# Thermocouple-Interface-5V.net
KiCad netlist of a schematic drawn in EAGLE
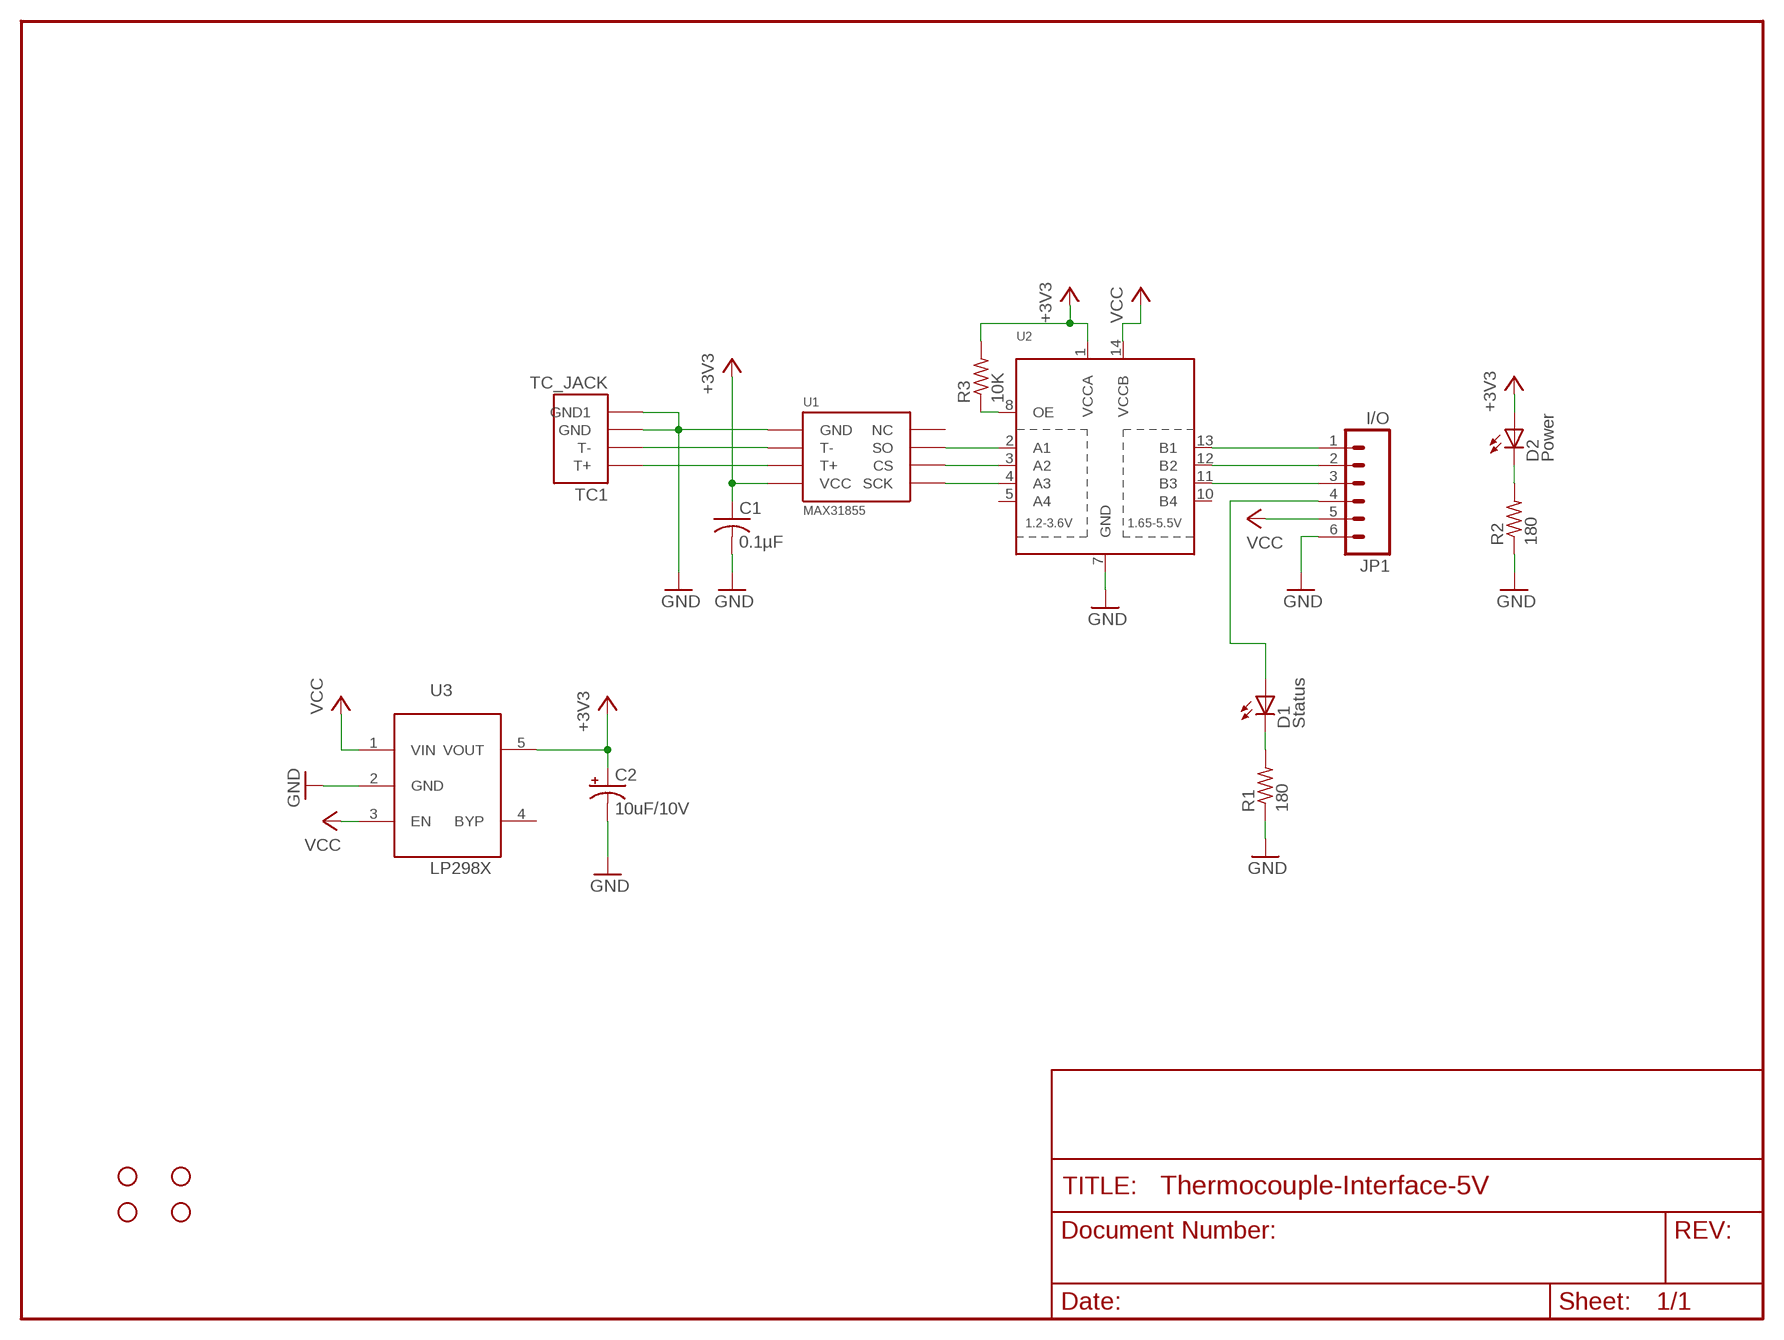
[diagram p0: schematic, sheet 1]

(export (version "E")
  (design (tool "Eeschema 10.0.6"))
  (components
    (comp (ref "C1")
      (value "0.1µF")
      (footprint "eagle-import:C0603")
      (libsource (lib "eagle-import") (part "C-USC0603"))
    )
    (comp (ref "C2")
      (value "10uF/10V")
      (footprint "eagle-import:A_3216-18R")
      (libsource (lib "eagle-import") (part "CPOL-USA/3216-18R"))
    )
    (comp (ref "D1")
      (value "Status")
      (footprint "eagle-import:CHIP-LED0805")
      (libsource (lib "eagle-import") (part "LEDCHIP-LED0805"))
    )
    (comp (ref "D2")
      (value "Power")
      (footprint "eagle-import:CHIP-LED0805")
      (libsource (lib "eagle-import") (part "LEDCHIP-LED0805"))
    )
    (comp (ref "JP1")
      (value "I/O")
      (footprint "eagle-import:1X06")
      (libsource (lib "eagle-import") (part "M06SIP"))
    )
    (comp (ref "R1")
      (value "180")
      (footprint "eagle-import:R0603")
      (libsource (lib "eagle-import") (part "R-US_R0603"))
    )
    (comp (ref "R2")
      (value "180")
      (footprint "eagle-import:R0603")
      (libsource (lib "eagle-import") (part "R-US_R0603"))
    )
    (comp (ref "R3")
      (value "10K")
      (footprint "eagle-import:R0603")
      (libsource (lib "eagle-import") (part "R-US_R0603"))
    )
    (comp (ref "TC1")
      (value "TC_JACK")
      (footprint "eagle-import:TC_JACK")
      (libsource (lib "eagle-import") (part "TC_JACK"))
    )
    (comp (ref "U$1")
      (value "STAND-OFF")
      (footprint "eagle-import:STAND-OFF")
      (libsource (lib "eagle-import") (part "STAND-OFF"))
    )
    (comp (ref "U$2")
      (value "STAND-OFF")
      (footprint "eagle-import:STAND-OFF")
      (libsource (lib "eagle-import") (part "STAND-OFF"))
    )
    (comp (ref "U$3")
      (value "STAND-OFF")
      (footprint "eagle-import:STAND-OFF")
      (libsource (lib "eagle-import") (part "STAND-OFF"))
    )
    (comp (ref "U$4")
      (value "STAND-OFF")
      (footprint "eagle-import:STAND-OFF")
      (libsource (lib "eagle-import") (part "STAND-OFF"))
    )
    (comp (ref "U1")
      (value "MAX31855")
      (footprint "eagle-import:SOIC-8")
      (libsource (lib "eagle-import") (part "MAX6675MAX31855"))
    )
    (comp (ref "U2")
      (value "TXB0104PWR")
      (footprint "eagle-import:TSSOP14")
      (libsource (lib "eagle-import") (part "TXB0104PWR"))
    )
    (comp (ref "U3")
      (value "LP298XS")
      (footprint "eagle-import:SOT23-5L")
      (libsource (lib "eagle-import") (part "LP298XS"))
    )
  )
  (nets
    (net (code "1") (name "+3V3") (class "Default")
      (node (ref "C1") (pin "1") (pinfunction "1_1") (pintype "passive"))
      (node (ref "C2") (pin "+") (pinfunction "+_+") (pintype "passive"))
      (node (ref "D2") (pin "A") (pinfunction "A_A") (pintype "passive"))
      (node (ref "R3") (pin "2") (pinfunction "2_2") (pintype "passive"))
      (node (ref "U1") (pin "VCC") (pinfunction "VCC_VCC") (pintype "bidirectional"))
      (node (ref "U2") (pin "1") (pinfunction "VCCA_1") (pintype "bidirectional"))
      (node (ref "U3") (pin "5") (pinfunction "VOUT_5") (pintype "bidirectional"))
    )
    (net (code "2") (name "GND") (class "Default")
      (node (ref "C1") (pin "2") (pinfunction "2_2") (pintype "passive"))
      (node (ref "C2") (pin "-") (pinfunction "-_-") (pintype "passive"))
      (node (ref "JP1") (pin "6") (pinfunction "6_6") (pintype "passive"))
      (node (ref "R1") (pin "1") (pinfunction "1_1") (pintype "passive"))
      (node (ref "R2") (pin "1") (pinfunction "1_1") (pintype "passive"))
      (node (ref "TC1") (pin "P$1") (pinfunction "GND_P$1") (pintype "bidirectional"))
      (node (ref "TC1") (pin "P$2") (pinfunction "GND1_P$2") (pintype "bidirectional"))
      (node (ref "U1") (pin "GND") (pinfunction "GND_GND") (pintype "bidirectional"))
      (node (ref "U2") (pin "7") (pinfunction "GND_7") (pintype "bidirectional"))
      (node (ref "U3") (pin "2") (pinfunction "GND_2") (pintype "bidirectional"))
    )
    (net (code "3") (name "Net-(D1-PadA)") (class "Default")
      (node (ref "D1") (pin "A") (pinfunction "A_A") (pintype "passive"))
      (node (ref "JP1") (pin "4") (pinfunction "4_4") (pintype "passive"))
    )
    (net (code "4") (name "Net-(D1-PadC)") (class "Default")
      (node (ref "D1") (pin "C") (pinfunction "C_C") (pintype "passive"))
      (node (ref "R1") (pin "2") (pinfunction "2_2") (pintype "passive"))
    )
    (net (code "5") (name "Net-(D2-PadC)") (class "Default")
      (node (ref "D2") (pin "C") (pinfunction "C_C") (pintype "passive"))
      (node (ref "R2") (pin "2") (pinfunction "2_2") (pintype "passive"))
    )
    (net (code "6") (name "Net-(TC1-PadT+)") (class "Default")
      (node (ref "TC1") (pin "T+") (pinfunction "T+_T+") (pintype "bidirectional"))
      (node (ref "U1") (pin "T+") (pinfunction "T+_T+") (pintype "bidirectional"))
    )
    (net (code "7") (name "Net-(TC1-PadT-)") (class "Default")
      (node (ref "TC1") (pin "T-") (pinfunction "T-_T-") (pintype "bidirectional"))
      (node (ref "U1") (pin "T-") (pinfunction "T-_T-") (pintype "bidirectional"))
    )
    (net (code "8") (name "Net-(U2-A1)") (class "Default")
      (node (ref "U1") (pin "SO") (pinfunction "SO_SO") (pintype "bidirectional"))
      (node (ref "U2") (pin "2") (pinfunction "A1_2") (pintype "bidirectional"))
    )
    (net (code "9") (name "Net-(U2-A2)") (class "Default")
      (node (ref "U1") (pin "CS") (pinfunction "CS_CS") (pintype "bidirectional"))
      (node (ref "U2") (pin "3") (pinfunction "A2_3") (pintype "bidirectional"))
    )
    (net (code "10") (name "Net-(U2-A3)") (class "Default")
      (node (ref "U1") (pin "SCK") (pinfunction "SCK_SCK") (pintype "bidirectional"))
      (node (ref "U2") (pin "4") (pinfunction "A3_4") (pintype "bidirectional"))
    )
    (net (code "11") (name "Net-(U2-B1)") (class "Default")
      (node (ref "JP1") (pin "1") (pinfunction "1_1") (pintype "passive"))
      (node (ref "U2") (pin "13") (pinfunction "B1_13") (pintype "bidirectional"))
    )
    (net (code "12") (name "Net-(U2-B2)") (class "Default")
      (node (ref "JP1") (pin "2") (pinfunction "2_2") (pintype "passive"))
      (node (ref "U2") (pin "12") (pinfunction "B2_12") (pintype "bidirectional"))
    )
    (net (code "13") (name "Net-(U2-B3)") (class "Default")
      (node (ref "JP1") (pin "3") (pinfunction "3_3") (pintype "passive"))
      (node (ref "U2") (pin "11") (pinfunction "B3_11") (pintype "bidirectional"))
    )
    (net (code "14") (name "Net-(U2-OE)") (class "Default")
      (node (ref "R3") (pin "1") (pinfunction "1_1") (pintype "passive"))
      (node (ref "U2") (pin "8") (pinfunction "OE_8") (pintype "bidirectional"))
    )
    (net (code "15") (name "VCC") (class "Default")
      (node (ref "JP1") (pin "5") (pinfunction "5_5") (pintype "passive"))
      (node (ref "U2") (pin "14") (pinfunction "VCCB_14") (pintype "bidirectional"))
      (node (ref "U3") (pin "1") (pinfunction "VIN_1") (pintype "bidirectional"))
      (node (ref "U3") (pin "3") (pinfunction "EN_3") (pintype "bidirectional"))
    )
    (net (code "16") (name "unconnected-(U1-PadNC)") (class "Default")
      (node (ref "U1") (pin "NC") (pinfunction "NC_NC") (pintype "no_connect"))
    )
    (net (code "17") (name "unconnected-(U2-A4-Pad5)") (class "Default")
      (node (ref "U2") (pin "5") (pinfunction "A4_5") (pintype "bidirectional"))
    )
    (net (code "18") (name "unconnected-(U2-B4-Pad10)") (class "Default")
      (node (ref "U2") (pin "10") (pinfunction "B4_10") (pintype "bidirectional"))
    )
    (net (code "19") (name "unconnected-(U3-BYP-Pad4)") (class "Default")
      (node (ref "U3") (pin "4") (pinfunction "BYP_4") (pintype "bidirectional"))
    )
  )
)
